# EC11_breakout.net
KiCad netlist of a schematic drawn in EAGLE
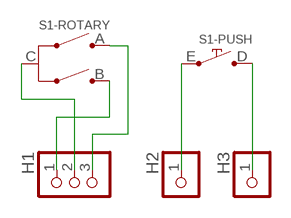
[diagram p0: schematic, sheet 1]

(export (version "E")
  (design (tool "Eeschema 10.0.6"))
  (components
    (comp (ref "H1")
      (value "PINHD-1X03ROUND")
      (footprint "eagle-import:1X03-ROUND")
      (libsource (lib "eagle-import") (part "PINHD-1X03ROUND"))
    )
    (comp (ref "H2")
      (value "PINHD-1X01ROUND")
      (footprint "eagle-import:1X01-ROUND")
      (libsource (lib "eagle-import") (part "PINHD-1X01ROUND"))
    )
    (comp (ref "H3")
      (value "PINHD-1X01ROUND")
      (footprint "eagle-import:1X01-ROUND")
      (libsource (lib "eagle-import") (part "PINHD-1X01ROUND"))
    )
    (comp (ref "S1")
      (value "EC11")
      (footprint "eagle-import:EC11")
      (libsource (lib "eagle-import") (part "EC11"))
    )
  )
  (nets
    (net (code "1") (name "Net-(H1-Pad1)") (class "Default")
      (node (ref "H1") (pin "1") (pinfunction "1_1") (pintype "passive"))
      (node (ref "S1") (pin "B") (pinfunction "B_B") (pintype "passive"))
    )
    (net (code "2") (name "Net-(H1-Pad2)") (class "Default")
      (node (ref "H1") (pin "2") (pinfunction "2_2") (pintype "passive"))
      (node (ref "S1") (pin "C") (pinfunction "C_C") (pintype "passive"))
    )
    (net (code "3") (name "Net-(H1-Pad3)") (class "Default")
      (node (ref "H1") (pin "3") (pinfunction "3_3") (pintype "passive"))
      (node (ref "S1") (pin "A") (pinfunction "A_A") (pintype "passive"))
    )
    (net (code "4") (name "Net-(H2-Pad1)") (class "Default")
      (node (ref "H2") (pin "1") (pinfunction "1_1") (pintype "passive"))
      (node (ref "S1") (pin "E") (pinfunction "E_E") (pintype "passive"))
    )
    (net (code "5") (name "Net-(H3-Pad1)") (class "Default")
      (node (ref "H3") (pin "1") (pinfunction "1_1") (pintype "passive"))
      (node (ref "S1") (pin "D") (pinfunction "D_D") (pintype "passive"))
    )
  )
)
